# 0_2.net
KiCad netlist of a schematic drawn in EAGLE
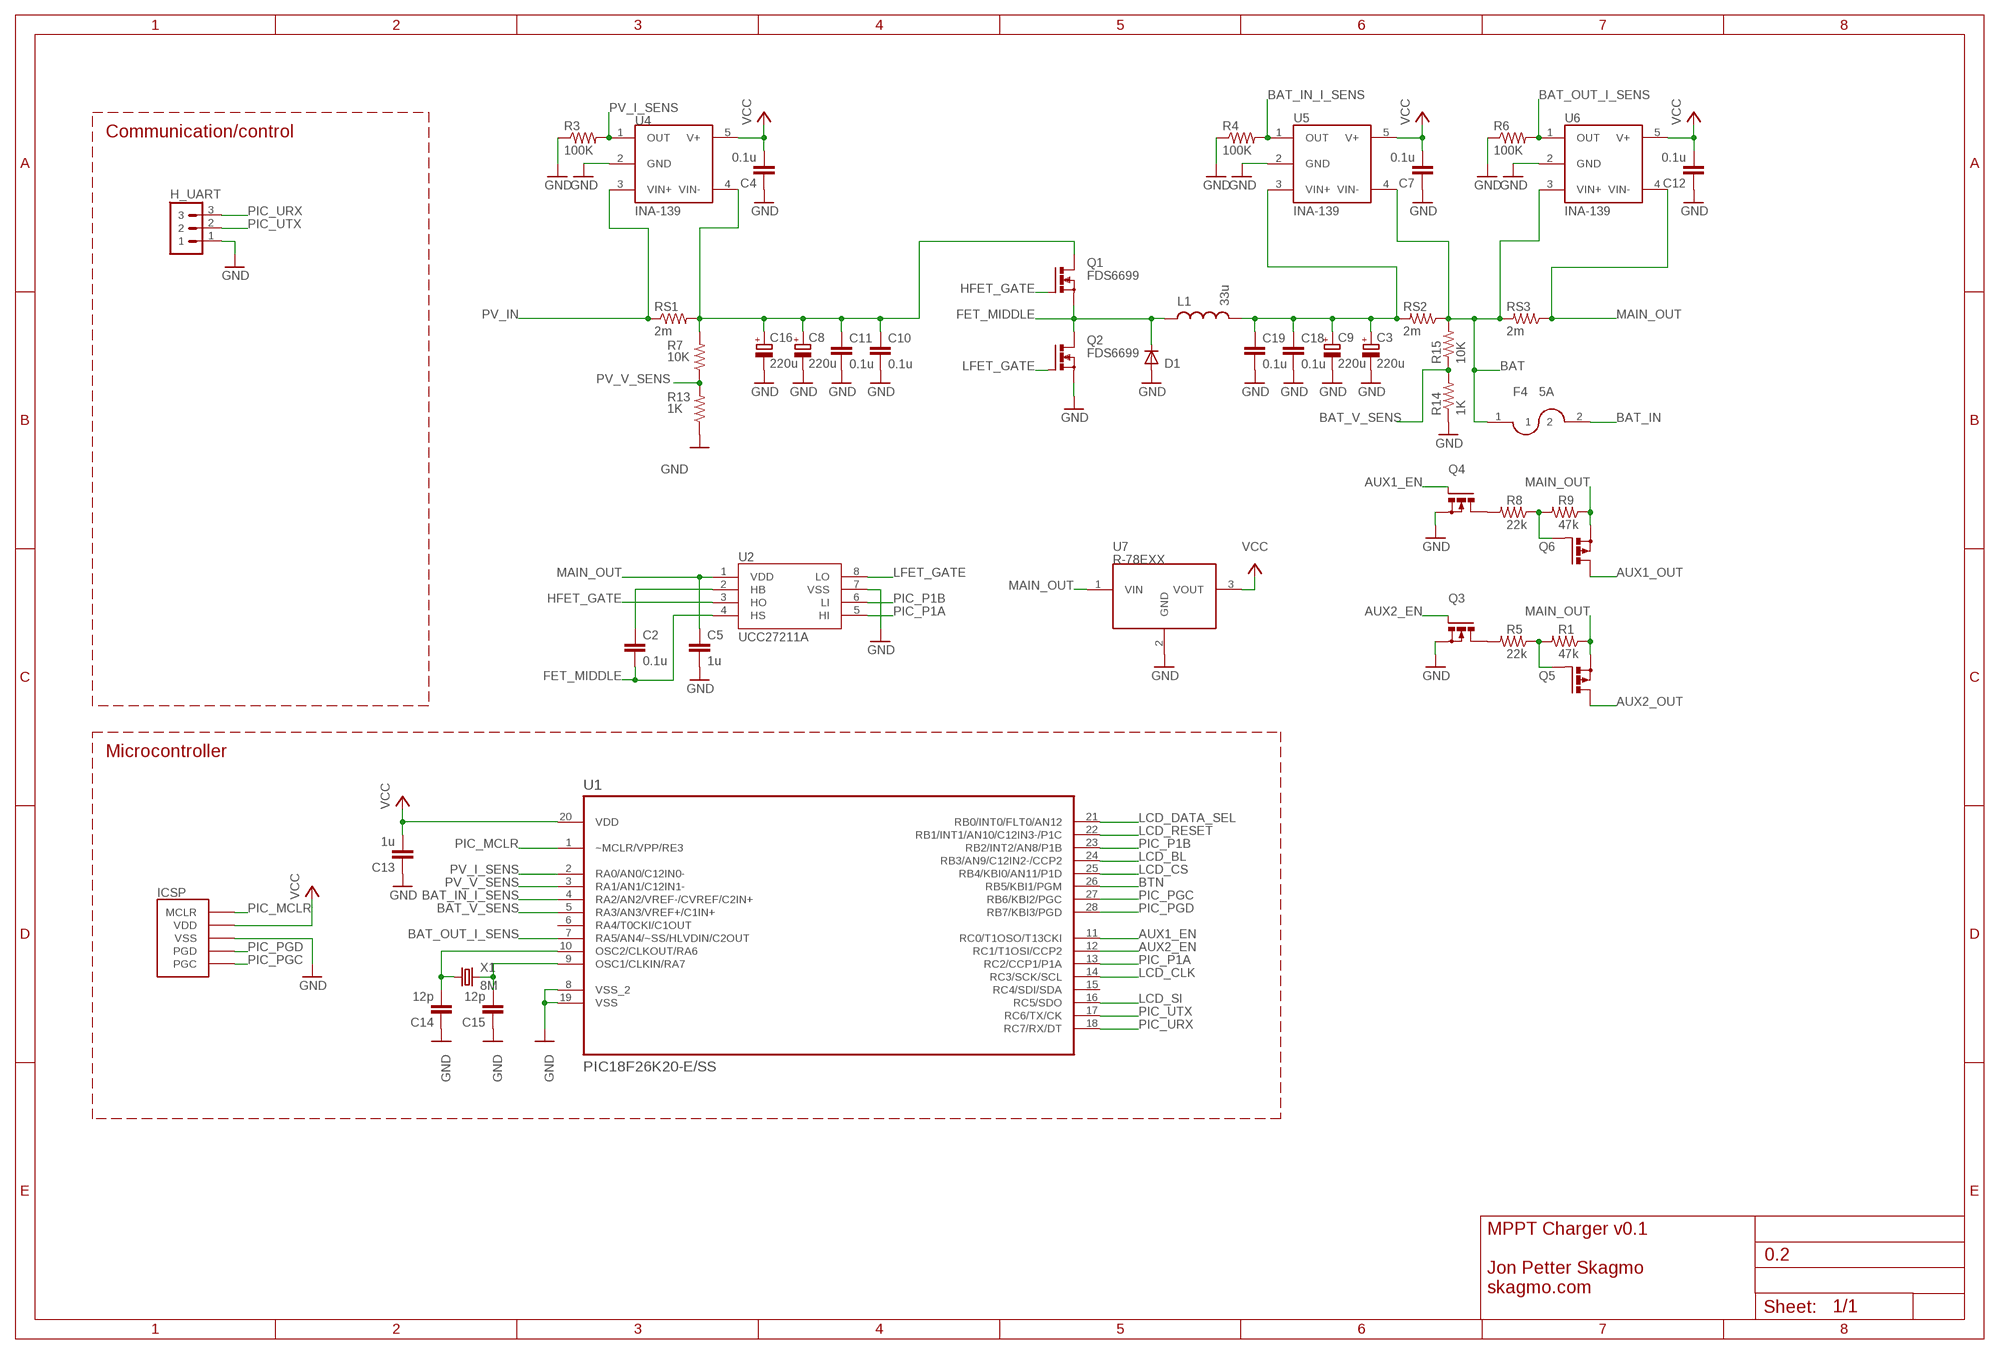
[diagram p0: schematic, sheet 1]

(export (version "E")
  (design (tool "Eeschema 10.0.6"))
  (components
    (comp (ref "C2")
      (value "0.1u")
      (footprint "eagle-import:0603")
      (libsource (lib "eagle-import") (part "CAP0603"))
    )
    (comp (ref "C3")
      (value "220u")
      (footprint "eagle-import:E3,5-8")
      (fields (field (name "PARTNO") "35ZLH220MEFC8X11.5"))
      (libsource (lib "eagle-import") (part "CPOL-EUE3.5-8"))
    )
    (comp (ref "C4")
      (value "0.1u")
      (footprint "eagle-import:0603")
      (libsource (lib "eagle-import") (part "CAP0603"))
    )
    (comp (ref "C5")
      (value "1u")
      (footprint "eagle-import:0603")
      (libsource (lib "eagle-import") (part "CAP0603"))
    )
    (comp (ref "C7")
      (value "0.1u")
      (footprint "eagle-import:0603")
      (libsource (lib "eagle-import") (part "CAP0603"))
    )
    (comp (ref "C8")
      (value "220u")
      (footprint "eagle-import:E3,5-8")
      (fields (field (name "PARTNO") "35ZLH220MEFC8X11.5"))
      (libsource (lib "eagle-import") (part "CPOL-EUE3.5-8"))
    )
    (comp (ref "C9")
      (value "220u")
      (footprint "eagle-import:E3,5-8")
      (fields (field (name "PARTNO") "35ZLH220MEFC8X11.5"))
      (libsource (lib "eagle-import") (part "CPOL-EUE3.5-8"))
    )
    (comp (ref "C10")
      (value "0.1u")
      (footprint "eagle-import:0603")
      (libsource (lib "eagle-import") (part "CAP0603"))
    )
    (comp (ref "C11")
      (value "0.1u")
      (footprint "eagle-import:0603")
      (libsource (lib "eagle-import") (part "CAP0603"))
    )
    (comp (ref "C12")
      (value "0.1u")
      (footprint "eagle-import:0603")
      (libsource (lib "eagle-import") (part "CAP0603"))
    )
    (comp (ref "C13")
      (value "1u")
      (footprint "eagle-import:0603")
      (libsource (lib "eagle-import") (part "CAP0603"))
    )
    (comp (ref "C14")
      (value "12p")
      (footprint "eagle-import:0603")
      (libsource (lib "eagle-import") (part "CAP0603"))
    )
    (comp (ref "C15")
      (value "12p")
      (footprint "eagle-import:0603")
      (libsource (lib "eagle-import") (part "CAP0603"))
    )
    (comp (ref "C16")
      (value "220u")
      (footprint "eagle-import:E3,5-8")
      (fields (field (name "PARTNO") "35ZLH220MEFC8X11.5"))
      (libsource (lib "eagle-import") (part "CPOL-EUE3.5-8"))
    )
    (comp (ref "C18")
      (value "0.1u")
      (footprint "eagle-import:0603")
      (libsource (lib "eagle-import") (part "CAP0603"))
    )
    (comp (ref "C19")
      (value "0.1u")
      (footprint "eagle-import:0603")
      (libsource (lib "eagle-import") (part "CAP0603"))
    )
    (comp (ref "D1")
      (value "DIODESMB")
      (footprint "eagle-import:SMB-DIODE")
      (fields (field (name "PARTNO") "SK54B-LTP"))
      (libsource (lib "eagle-import") (part "DIODESMB"))
    )
    (comp (ref "F4")
      (value "5A")
      (footprint "eagle-import:1206")
      (fields (field (name "PARTNO") "C1T 5"))
      (libsource (lib "eagle-import") (part "FUSE1206"))
    )
    (comp (ref "H_UART")
      (value "H1X3_XH")
      (footprint "eagle-import:CON_B3B-XH-A")
      (fields (field (name "PARTNO") "B3B-XH-A (LF)(SN)(P)"))
      (libsource (lib "eagle-import") (part "H1X3_XH"))
    )
    (comp (ref "ICSP")
      (value "1X5_ICSP")
      (footprint "eagle-import:1X5_2MM")
      (libsource (lib "eagle-import") (part "1X5_ICSP"))
    )
    (comp (ref "L1")
      (value "33u")
      (footprint "eagle-import:IHLP-6767")
      (fields (field (name "PARTNO") "IHLP6767GZER330M11"))
      (libsource (lib "eagle-import") (part "INDUCTORIHLP-6767"))
    )
    (comp (ref "Q1")
      (value "FDS6699")
      (footprint "eagle-import:SO08")
      (fields (field (name "PARTNO") "SI4128DY-T1-GE3"))
      (libsource (lib "eagle-import") (part "PMOSFET_N"))
    )
    (comp (ref "Q2")
      (value "FDS6699")
      (footprint "eagle-import:SO08")
      (fields (field (name "PARTNO") "SI4128DY-T1-GE3"))
      (libsource (lib "eagle-import") (part "PMOSFET_N"))
    )
    (comp (ref "Q3")
      (value "MOSFET_N_SOT23-3")
      (footprint "eagle-import:SOT23-3")
      (fields (field (name "PARTNO") "BSH103,215"))
      (libsource (lib "eagle-import") (part "MOSFET_N_SOT23-3"))
    )
    (comp (ref "Q4")
      (value "MOSFET_N_SOT23-3")
      (footprint "eagle-import:SOT23-3")
      (fields (field (name "PARTNO") "BSH103,215"))
      (libsource (lib "eagle-import") (part "MOSFET_N_SOT23-3"))
    )
    (comp (ref "Q5")
      (value "PMOSFET_P")
      (footprint "eagle-import:SO08")
      (fields (field (name "PARTNO") "FDS6681Z"))
      (libsource (lib "eagle-import") (part "PMOSFET_P"))
    )
    (comp (ref "Q6")
      (value "PMOSFET_P")
      (footprint "eagle-import:SO08")
      (fields (field (name "PARTNO") "FDS6681Z"))
      (libsource (lib "eagle-import") (part "PMOSFET_P"))
    )
    (comp (ref "R1")
      (value "47k")
      (footprint "eagle-import:0603")
      (libsource (lib "eagle-import") (part "RESISTOR0603"))
    )
    (comp (ref "R3")
      (value "100K")
      (footprint "eagle-import:0603")
      (libsource (lib "eagle-import") (part "RESISTOR0603"))
    )
    (comp (ref "R4")
      (value "100K")
      (footprint "eagle-import:0603")
      (libsource (lib "eagle-import") (part "RESISTOR0603"))
    )
    (comp (ref "R5")
      (value "22k")
      (footprint "eagle-import:0603")
      (libsource (lib "eagle-import") (part "RESISTOR0603"))
    )
    (comp (ref "R6")
      (value "100K")
      (footprint "eagle-import:0603")
      (libsource (lib "eagle-import") (part "RESISTOR0603"))
    )
    (comp (ref "R7")
      (value "10K")
      (footprint "eagle-import:0603")
      (libsource (lib "eagle-import") (part "RESISTOR0603"))
    )
    (comp (ref "R8")
      (value "22k")
      (footprint "eagle-import:0603")
      (libsource (lib "eagle-import") (part "RESISTOR0603"))
    )
    (comp (ref "R9")
      (value "47k")
      (footprint "eagle-import:0603")
      (libsource (lib "eagle-import") (part "RESISTOR0603"))
    )
    (comp (ref "R13")
      (value "1K")
      (footprint "eagle-import:0603")
      (libsource (lib "eagle-import") (part "RESISTOR0603"))
    )
    (comp (ref "R14")
      (value "1K")
      (footprint "eagle-import:0603")
      (libsource (lib "eagle-import") (part "RESISTOR0603"))
    )
    (comp (ref "R15")
      (value "10K")
      (footprint "eagle-import:0603")
      (libsource (lib "eagle-import") (part "RESISTOR0603"))
    )
    (comp (ref "RS1")
      (value "2m")
      (footprint "eagle-import:R3225")
      (fields (field (name "PARTNO") "PMR25HZPFV2L00"))
      (libsource (lib "eagle-import") (part "R-US_R3225"))
    )
    (comp (ref "RS2")
      (value "2m")
      (footprint "eagle-import:R3225")
      (fields (field (name "PARTNO") "PMR25HZPFV2L00"))
      (libsource (lib "eagle-import") (part "R-US_R3225"))
    )
    (comp (ref "RS3")
      (value "2m")
      (footprint "eagle-import:R3225")
      (fields (field (name "PARTNO") "PMR25HZPFV2L00"))
      (libsource (lib "eagle-import") (part "R-US_R3225"))
    )
    (comp (ref "U1")
      (value "PIC18F26K20-E/SS")
      (footprint "eagle-import:SOP65P780X200-28N")
      (fields (field (name "PARTNO") "PIC18F26K22-I/SS"))
      (libsource (lib "eagle-import") (part "PIC18F26K20-E/SS"))
    )
    (comp (ref "U2")
      (value "UCC27211A")
      (footprint "eagle-import:SO08")
      (fields (field (name "PARTNO") "UCC27211D"))
      (libsource (lib "eagle-import") (part "UCC27211A"))
    )
    (comp (ref "U4")
      (value "INA-139")
      (footprint "eagle-import:SOT23-5")
      (fields (field (name "PARTNO") "INA139NA/250"))
      (libsource (lib "eagle-import") (part "INA-169"))
    )
    (comp (ref "U5")
      (value "INA-139")
      (footprint "eagle-import:SOT23-5")
      (fields (field (name "PARTNO") "INA139NA/250"))
      (libsource (lib "eagle-import") (part "INA-169"))
    )
    (comp (ref "U6")
      (value "INA-139")
      (footprint "eagle-import:SOT23-5")
      (fields (field (name "PARTNO") "INA139NA/250"))
      (libsource (lib "eagle-import") (part "INA-169"))
    )
    (comp (ref "U7")
      (value "R-78EXX")
      (footprint "eagle-import:R-78EXX")
      (fields (field (name "PARTNO") "R-78E3.3-0.5"))
      (libsource (lib "eagle-import") (part "R-78EXX"))
    )
    (comp (ref "X1")
      (value "8M")
      (footprint "eagle-import:TXC-7A")
      (fields (field (name "PARTNO") "7A-8.000MAAE-T"))
      (libsource (lib "eagle-import") (part "TXC-7A"))
    )
  )
  (nets
    (net (code "1") (name "/AUX1_EN") (class "Default")
      (node (ref "Q4") (pin "1") (pinfunction "G_1") (pintype "passive"))
      (node (ref "U1") (pin "11") (pinfunction "RC0/T1OSO/T13CKI_11") (pintype "bidirectional"))
    )
    (net (code "2") (name "/AUX1_OUT") (class "Default")
      (node (ref "Q6") (pin "5") (pinfunction "D_5") (pintype "passive"))
      (node (ref "Q6") (pin "6") (pinfunction "D_6") (pintype "passive"))
      (node (ref "Q6") (pin "7") (pinfunction "D_7") (pintype "passive"))
      (node (ref "Q6") (pin "8") (pinfunction "D_8") (pintype "passive"))
    )
    (net (code "3") (name "/AUX2_EN") (class "Default")
      (node (ref "Q3") (pin "1") (pinfunction "G_1") (pintype "passive"))
      (node (ref "U1") (pin "12") (pinfunction "RC1/T1OSI/CCP2_12") (pintype "bidirectional"))
    )
    (net (code "4") (name "/AUX2_OUT") (class "Default")
      (node (ref "Q5") (pin "5") (pinfunction "D_5") (pintype "passive"))
      (node (ref "Q5") (pin "6") (pinfunction "D_6") (pintype "passive"))
      (node (ref "Q5") (pin "7") (pinfunction "D_7") (pintype "passive"))
      (node (ref "Q5") (pin "8") (pinfunction "D_8") (pintype "passive"))
    )
    (net (code "5") (name "/BAT") (class "Default")
      (node (ref "F4") (pin "1") (pinfunction "1_1") (pintype "bidirectional"))
      (node (ref "R15") (pin "2") (pinfunction "2_2") (pintype "passive"))
      (node (ref "RS2") (pin "1") (pinfunction "1_1") (pintype "passive"))
      (node (ref "RS3") (pin "2") (pinfunction "2_2") (pintype "passive"))
      (node (ref "U5") (pin "4") (pinfunction "VIN-_4") (pintype "bidirectional"))
      (node (ref "U6") (pin "3") (pinfunction "VIN+_3") (pintype "bidirectional"))
    )
    (net (code "6") (name "/BAT_IN") (class "Default")
      (node (ref "F4") (pin "2") (pinfunction "2_2") (pintype "bidirectional"))
    )
    (net (code "7") (name "/BAT_IN_I_SENS") (class "Default")
      (node (ref "R4") (pin "2") (pinfunction "2_2") (pintype "passive"))
      (node (ref "U1") (pin "4") (pinfunction "RA2/AN2/VREF-/CVREF/C2IN+_4") (pintype "bidirectional"))
      (node (ref "U5") (pin "1") (pinfunction "OUT_1") (pintype "bidirectional"))
    )
    (net (code "8") (name "/BAT_OUT_I_SENS") (class "Default")
      (node (ref "R6") (pin "2") (pinfunction "2_2") (pintype "passive"))
      (node (ref "U1") (pin "7") (pinfunction "RA5/AN4/~{SS/HLVDIN/C2OUT}_7") (pintype "bidirectional"))
      (node (ref "U6") (pin "1") (pinfunction "OUT_1") (pintype "bidirectional"))
    )
    (net (code "9") (name "/BAT_V_SENS") (class "Default")
      (node (ref "R14") (pin "2") (pinfunction "2_2") (pintype "passive"))
      (node (ref "R15") (pin "1") (pinfunction "1_1") (pintype "passive"))
      (node (ref "U1") (pin "5") (pinfunction "RA3/AN3/VREF+/C1IN+_5") (pintype "bidirectional"))
    )
    (net (code "10") (name "/BTN") (class "Default")
      (node (ref "U1") (pin "26") (pinfunction "RB5/KBI1/PGM_26") (pintype "bidirectional"))
    )
    (net (code "11") (name "/FET_MIDDLE") (class "Default")
      (node (ref "C2") (pin "2") (pinfunction "2_2") (pintype "passive"))
      (node (ref "D1") (pin "C") (pinfunction "C_C") (pintype "passive"))
      (node (ref "L1") (pin "P$1") (pinfunction "1_P$1") (pintype "passive"))
      (node (ref "Q1") (pin "1") (pinfunction "S_1") (pintype "passive"))
      (node (ref "Q1") (pin "2") (pinfunction "S_2") (pintype "passive"))
      (node (ref "Q1") (pin "3") (pinfunction "S_3") (pintype "passive"))
      (node (ref "Q2") (pin "5") (pinfunction "D_5") (pintype "passive"))
      (node (ref "Q2") (pin "6") (pinfunction "D_6") (pintype "passive"))
      (node (ref "Q2") (pin "7") (pinfunction "D_7") (pintype "passive"))
      (node (ref "Q2") (pin "8") (pinfunction "D_8") (pintype "passive"))
      (node (ref "U2") (pin "4") (pinfunction "HS_4") (pintype "bidirectional"))
    )
    (net (code "12") (name "/HFET_GATE") (class "Default")
      (node (ref "Q1") (pin "4") (pinfunction "G_4") (pintype "passive"))
      (node (ref "U2") (pin "3") (pinfunction "HO_3") (pintype "bidirectional"))
    )
    (net (code "13") (name "/LCD_BL") (class "Default")
      (node (ref "U1") (pin "24") (pinfunction "RB3/AN9/C12IN2-/CCP2_24") (pintype "bidirectional"))
    )
    (net (code "14") (name "/LCD_CLK") (class "Default")
      (node (ref "U1") (pin "14") (pinfunction "RC3/SCK/SCL_14") (pintype "bidirectional"))
    )
    (net (code "15") (name "/LCD_CS") (class "Default")
      (node (ref "U1") (pin "25") (pinfunction "RB4/KBI0/AN11/P1D_25") (pintype "bidirectional"))
    )
    (net (code "16") (name "/LCD_DATA_SEL") (class "Default")
      (node (ref "U1") (pin "21") (pinfunction "RB0/INT0/FLT0/AN12_21") (pintype "bidirectional"))
    )
    (net (code "17") (name "/LCD_RESET") (class "Default")
      (node (ref "U1") (pin "22") (pinfunction "RB1/INT1/AN10/C12IN3-/P1C_22") (pintype "bidirectional"))
    )
    (net (code "18") (name "/LCD_SI") (class "Default")
      (node (ref "U1") (pin "16") (pinfunction "RC5/SDO_16") (pintype "bidirectional"))
    )
    (net (code "19") (name "/LFET_GATE") (class "Default")
      (node (ref "Q2") (pin "4") (pinfunction "G_4") (pintype "passive"))
      (node (ref "U2") (pin "8") (pinfunction "LO_8") (pintype "bidirectional"))
    )
    (net (code "20") (name "/MAIN_OUT") (class "Default")
      (node (ref "C5") (pin "1") (pinfunction "1_1") (pintype "passive"))
      (node (ref "Q5") (pin "1") (pinfunction "S_1") (pintype "passive"))
      (node (ref "Q5") (pin "2") (pinfunction "S_2") (pintype "passive"))
      (node (ref "Q5") (pin "3") (pinfunction "S_3") (pintype "passive"))
      (node (ref "Q6") (pin "1") (pinfunction "S_1") (pintype "passive"))
      (node (ref "Q6") (pin "2") (pinfunction "S_2") (pintype "passive"))
      (node (ref "Q6") (pin "3") (pinfunction "S_3") (pintype "passive"))
      (node (ref "R1") (pin "1") (pinfunction "1_1") (pintype "passive"))
      (node (ref "R9") (pin "1") (pinfunction "1_1") (pintype "passive"))
      (node (ref "RS3") (pin "1") (pinfunction "1_1") (pintype "passive"))
      (node (ref "U2") (pin "1") (pinfunction "VDD_1") (pintype "bidirectional"))
      (node (ref "U6") (pin "4") (pinfunction "VIN-_4") (pintype "bidirectional"))
      (node (ref "U7") (pin "1") (pinfunction "VIN_1") (pintype "bidirectional"))
    )
    (net (code "21") (name "/PIC_MCLR") (class "Default")
      (node (ref "ICSP") (pin "P$1") (pinfunction "MCLR_P$1") (pintype "bidirectional"))
      (node (ref "U1") (pin "1") (pinfunction "~{MCLR/VPP/RE3}_1") (pintype "input"))
    )
    (net (code "22") (name "/PIC_P1A") (class "Default")
      (node (ref "U1") (pin "13") (pinfunction "RC2/CCP1/P1A_13") (pintype "bidirectional"))
      (node (ref "U2") (pin "5") (pinfunction "HI_5") (pintype "bidirectional"))
    )
    (net (code "23") (name "/PIC_P1B") (class "Default")
      (node (ref "U1") (pin "23") (pinfunction "RB2/INT2/AN8/P1B_23") (pintype "bidirectional"))
      (node (ref "U2") (pin "6") (pinfunction "LI_6") (pintype "bidirectional"))
    )
    (net (code "24") (name "/PIC_PGC") (class "Default")
      (node (ref "ICSP") (pin "P$5") (pinfunction "PGC_P$5") (pintype "bidirectional"))
      (node (ref "U1") (pin "27") (pinfunction "RB6/KBI2/PGC_27") (pintype "bidirectional"))
    )
    (net (code "25") (name "/PIC_PGD") (class "Default")
      (node (ref "ICSP") (pin "P$4") (pinfunction "PGD_P$4") (pintype "bidirectional"))
      (node (ref "U1") (pin "28") (pinfunction "RB7/KBI3/PGD_28") (pintype "bidirectional"))
    )
    (net (code "26") (name "/PIC_URX") (class "Default")
      (node (ref "H_UART") (pin "3") (pinfunction "3_3") (pintype "passive"))
      (node (ref "U1") (pin "18") (pinfunction "RC7/RX/DT_18") (pintype "bidirectional"))
    )
    (net (code "27") (name "/PIC_UTX") (class "Default")
      (node (ref "H_UART") (pin "2") (pinfunction "2_2") (pintype "passive"))
      (node (ref "U1") (pin "17") (pinfunction "RC6/TX/CK_17") (pintype "bidirectional"))
    )
    (net (code "28") (name "/PV_IN") (class "Default")
      (node (ref "RS1") (pin "1") (pinfunction "1_1") (pintype "passive"))
      (node (ref "U4") (pin "3") (pinfunction "VIN+_3") (pintype "bidirectional"))
    )
    (net (code "29") (name "/PV_I_SENS") (class "Default")
      (node (ref "R3") (pin "2") (pinfunction "2_2") (pintype "passive"))
      (node (ref "U1") (pin "2") (pinfunction "RA0/AN0/C12IN0-_2") (pintype "bidirectional"))
      (node (ref "U4") (pin "1") (pinfunction "OUT_1") (pintype "bidirectional"))
    )
    (net (code "30") (name "/PV_V_SENS") (class "Default")
      (node (ref "R13") (pin "2") (pinfunction "2_2") (pintype "passive"))
      (node (ref "R7") (pin "1") (pinfunction "1_1") (pintype "passive"))
      (node (ref "U1") (pin "3") (pinfunction "RA1/AN1/C12IN1-_3") (pintype "bidirectional"))
    )
    (net (code "31") (name "GND") (class "Default")
      (node (ref "C10") (pin "2") (pinfunction "2_2") (pintype "passive"))
      (node (ref "C11") (pin "2") (pinfunction "2_2") (pintype "passive"))
      (node (ref "C12") (pin "1") (pinfunction "1_1") (pintype "passive"))
      (node (ref "C13") (pin "1") (pinfunction "1_1") (pintype "passive"))
      (node (ref "C14") (pin "1") (pinfunction "1_1") (pintype "passive"))
      (node (ref "C15") (pin "1") (pinfunction "1_1") (pintype "passive"))
      (node (ref "C16") (pin "-") (pinfunction "-_-") (pintype "passive"))
      (node (ref "C18") (pin "2") (pinfunction "2_2") (pintype "passive"))
      (node (ref "C19") (pin "2") (pinfunction "2_2") (pintype "passive"))
      (node (ref "C3") (pin "-") (pinfunction "-_-") (pintype "passive"))
      (node (ref "C4") (pin "1") (pinfunction "1_1") (pintype "passive"))
      (node (ref "C5") (pin "2") (pinfunction "2_2") (pintype "passive"))
      (node (ref "C7") (pin "1") (pinfunction "1_1") (pintype "passive"))
      (node (ref "C8") (pin "-") (pinfunction "-_-") (pintype "passive"))
      (node (ref "C9") (pin "-") (pinfunction "-_-") (pintype "passive"))
      (node (ref "D1") (pin "A") (pinfunction "A_A") (pintype "passive"))
      (node (ref "H_UART") (pin "1") (pinfunction "1_1") (pintype "passive"))
      (node (ref "ICSP") (pin "P$3") (pinfunction "VSS_P$3") (pintype "power_in"))
      (node (ref "Q2") (pin "1") (pinfunction "S_1") (pintype "passive"))
      (node (ref "Q2") (pin "2") (pinfunction "S_2") (pintype "passive"))
      (node (ref "Q2") (pin "3") (pinfunction "S_3") (pintype "passive"))
      (node (ref "Q3") (pin "2") (pinfunction "S_2") (pintype "passive"))
      (node (ref "Q4") (pin "2") (pinfunction "S_2") (pintype "passive"))
      (node (ref "R13") (pin "1") (pinfunction "1_1") (pintype "passive"))
      (node (ref "R14") (pin "1") (pinfunction "1_1") (pintype "passive"))
      (node (ref "R3") (pin "1") (pinfunction "1_1") (pintype "passive"))
      (node (ref "R4") (pin "1") (pinfunction "1_1") (pintype "passive"))
      (node (ref "R6") (pin "1") (pinfunction "1_1") (pintype "passive"))
      (node (ref "U1") (pin "19") (pinfunction "VSS_19") (pintype "power_in"))
      (node (ref "U1") (pin "8") (pinfunction "VSS_2_8") (pintype "power_in"))
      (node (ref "U2") (pin "7") (pinfunction "VSS_7") (pintype "bidirectional"))
      (node (ref "U4") (pin "2") (pinfunction "GND_2") (pintype "bidirectional"))
      (node (ref "U5") (pin "2") (pinfunction "GND_2") (pintype "bidirectional"))
      (node (ref "U6") (pin "2") (pinfunction "GND_2") (pintype "bidirectional"))
      (node (ref "U7") (pin "2") (pinfunction "GND_2") (pintype "bidirectional"))
    )
    (net (code "32") (name "Net-(L1-2)") (class "Default")
      (node (ref "C18") (pin "1") (pinfunction "1_1") (pintype "passive"))
      (node (ref "C19") (pin "1") (pinfunction "1_1") (pintype "passive"))
      (node (ref "C3") (pin "+") (pinfunction "+_+") (pintype "passive"))
      (node (ref "C9") (pin "+") (pinfunction "+_+") (pintype "passive"))
      (node (ref "L1") (pin "P$2") (pinfunction "2_P$2") (pintype "passive"))
      (node (ref "RS2") (pin "2") (pinfunction "2_2") (pintype "passive"))
      (node (ref "U5") (pin "3") (pinfunction "VIN+_3") (pintype "bidirectional"))
    )
    (net (code "33") (name "Net-(Q3-D)") (class "Default")
      (node (ref "Q3") (pin "3") (pinfunction "D_3") (pintype "passive"))
      (node (ref "R5") (pin "2") (pinfunction "2_2") (pintype "passive"))
    )
    (net (code "34") (name "Net-(Q4-D)") (class "Default")
      (node (ref "Q4") (pin "3") (pinfunction "D_3") (pintype "passive"))
      (node (ref "R8") (pin "2") (pinfunction "2_2") (pintype "passive"))
    )
    (net (code "35") (name "Net-(Q5-G)") (class "Default")
      (node (ref "Q5") (pin "4") (pinfunction "G_4") (pintype "passive"))
      (node (ref "R1") (pin "2") (pinfunction "2_2") (pintype "passive"))
      (node (ref "R5") (pin "1") (pinfunction "1_1") (pintype "passive"))
    )
    (net (code "36") (name "Net-(Q6-G)") (class "Default")
      (node (ref "Q6") (pin "4") (pinfunction "G_4") (pintype "passive"))
      (node (ref "R8") (pin "1") (pinfunction "1_1") (pintype "passive"))
      (node (ref "R9") (pin "2") (pinfunction "2_2") (pintype "passive"))
    )
    (net (code "37") (name "Net-(U1-OSC1{slash}CLKIN{slash}RA7)") (class "Default")
      (node (ref "C15") (pin "2") (pinfunction "2_2") (pintype "passive"))
      (node (ref "U1") (pin "9") (pinfunction "OSC1/CLKIN/RA7_9") (pintype "bidirectional"))
      (node (ref "X1") (pin "2") (pinfunction "2_2") (pintype "passive"))
    )
    (net (code "38") (name "Net-(U1-OSC2{slash}CLKOUT{slash}RA6)") (class "Default")
      (node (ref "C14") (pin "2") (pinfunction "2_2") (pintype "passive"))
      (node (ref "U1") (pin "10") (pinfunction "OSC2/CLKOUT/RA6_10") (pintype "bidirectional"))
      (node (ref "X1") (pin "1") (pinfunction "1_1") (pintype "passive"))
    )
    (net (code "39") (name "Net-(U2-HB)") (class "Default")
      (node (ref "C2") (pin "1") (pinfunction "1_1") (pintype "passive"))
      (node (ref "U2") (pin "2") (pinfunction "HB_2") (pintype "bidirectional"))
    )
    (net (code "40") (name "Net-(U4-VIN-)") (class "Default")
      (node (ref "C10") (pin "1") (pinfunction "1_1") (pintype "passive"))
      (node (ref "C11") (pin "1") (pinfunction "1_1") (pintype "passive"))
      (node (ref "C16") (pin "+") (pinfunction "+_+") (pintype "passive"))
      (node (ref "C8") (pin "+") (pinfunction "+_+") (pintype "passive"))
      (node (ref "Q1") (pin "5") (pinfunction "D_5") (pintype "passive"))
      (node (ref "Q1") (pin "6") (pinfunction "D_6") (pintype "passive"))
      (node (ref "Q1") (pin "7") (pinfunction "D_7") (pintype "passive"))
      (node (ref "Q1") (pin "8") (pinfunction "D_8") (pintype "passive"))
      (node (ref "R7") (pin "2") (pinfunction "2_2") (pintype "passive"))
      (node (ref "RS1") (pin "2") (pinfunction "2_2") (pintype "passive"))
      (node (ref "U4") (pin "4") (pinfunction "VIN-_4") (pintype "bidirectional"))
    )
    (net (code "41") (name "VCC") (class "Default")
      (node (ref "C12") (pin "2") (pinfunction "2_2") (pintype "passive"))
      (node (ref "C13") (pin "2") (pinfunction "2_2") (pintype "passive"))
      (node (ref "C4") (pin "2") (pinfunction "2_2") (pintype "passive"))
      (node (ref "C7") (pin "2") (pinfunction "2_2") (pintype "passive"))
      (node (ref "ICSP") (pin "P$2") (pinfunction "VDD_P$2") (pintype "power_in"))
      (node (ref "U1") (pin "20") (pinfunction "VDD_20") (pintype "power_in"))
      (node (ref "U4") (pin "5") (pinfunction "V+_5") (pintype "bidirectional"))
      (node (ref "U5") (pin "5") (pinfunction "V+_5") (pintype "bidirectional"))
      (node (ref "U6") (pin "5") (pinfunction "V+_5") (pintype "bidirectional"))
      (node (ref "U7") (pin "3") (pinfunction "VOUT_3") (pintype "bidirectional"))
    )
    (net (code "42") (name "unconnected-(U1-RA4{slash}T0CKI{slash}C1OUT-Pad6)") (class "Default")
      (node (ref "U1") (pin "6") (pinfunction "RA4/T0CKI/C1OUT_6") (pintype "bidirectional"))
    )
    (net (code "43") (name "unconnected-(U1-RC4{slash}SDI{slash}SDA-Pad15)") (class "Default")
      (node (ref "U1") (pin "15") (pinfunction "RC4/SDI/SDA_15") (pintype "bidirectional"))
    )
  )
)
